# Arduino-Pro-Mini-xkid.net
KiCad netlist of a schematic drawn in EAGLE
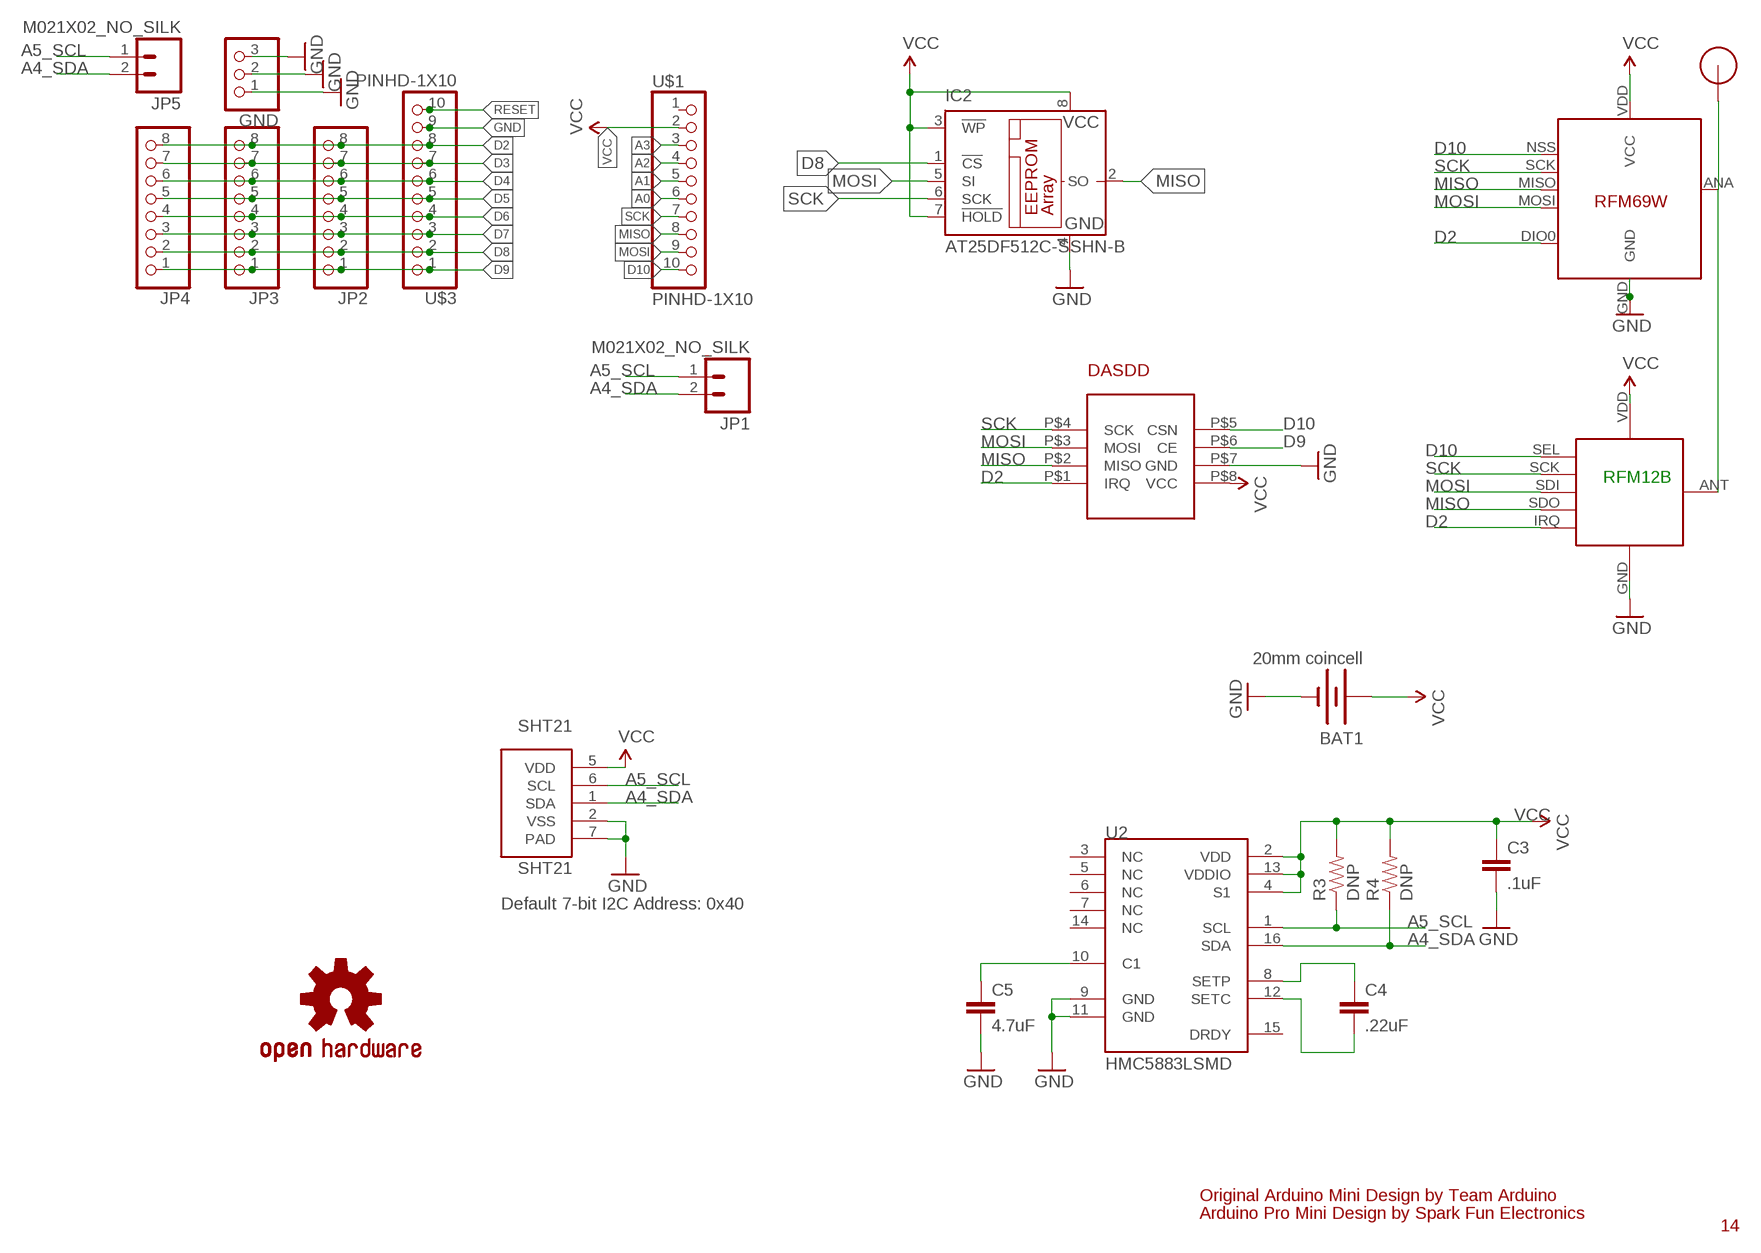
[diagram p0: schematic, sheet 1]

(export (version "E")
  (design (tool "Eeschema 10.0.6"))
  (components
    (comp (ref "BAT1")
      (value "20mm coincell")
      (footprint "eagle-import:BATTCON_20MM_4LEGS")
      (libsource (lib "eagle-import") (part "BATTERY20MM_4LEGS"))
    )
    (comp (ref "C3")
      (value ".1uF")
      (footprint "eagle-import:0603-CAP")
      (libsource (lib "eagle-import") (part "CAP0603-CAP"))
    )
    (comp (ref "C4")
      (value ".22uF")
      (footprint "eagle-import:0603-CAP")
      (libsource (lib "eagle-import") (part "CAP0603-CAP"))
    )
    (comp (ref "C5")
      (value "4.7uF")
      (footprint "eagle-import:0603-CAP")
      (libsource (lib "eagle-import") (part "CAP0603-CAP"))
    )
    (comp (ref "DASDD")
      (value "NRF24L01+_1.27")
      (footprint "eagle-import:NRF24L01_1.27")
      (libsource (lib "eagle-import") (part "NRF24L01+_1.27"))
    )
    (comp (ref "GND")
      (value "PINHD-1X3")
      (footprint "eagle-import:1X03")
      (libsource (lib "eagle-import") (part "PINHD-1X3"))
    )
    (comp (ref "IC2")
      (value "AT25DF512C-SSHN-B")
      (footprint "eagle-import:SO-08")
      (fields (field (name "MF") "MICROCHIP") (field (name "MPN") "25AA080/SN"))
      (libsource (lib "eagle-import") (part "25SNAA080"))
    )
    (comp (ref "JP1")
      (value "M021X02_NO_SILK")
      (footprint "eagle-import:1X02_NO_SILK")
      (libsource (lib "eagle-import") (part "M021X02_NO_SILK"))
    )
    (comp (ref "JP2")
      (value "PINHD-1X8CLEANBIG")
      (footprint "eagle-import:1X08-CLEANBIG")
      (libsource (lib "eagle-import") (part "PINHD-1X8CLEANBIG"))
    )
    (comp (ref "JP3")
      (value "PINHD-1X8CLEANBIG")
      (footprint "eagle-import:1X08-CLEANBIG")
      (libsource (lib "eagle-import") (part "PINHD-1X8CLEANBIG"))
    )
    (comp (ref "JP4")
      (value "PINHD-1X8CLEANBIG")
      (footprint "eagle-import:1X08-CLEANBIG")
      (libsource (lib "eagle-import") (part "PINHD-1X8CLEANBIG"))
    )
    (comp (ref "JP5")
      (value "M021X02_NO_SILK")
      (footprint "eagle-import:1X02_NO_SILK")
      (libsource (lib "eagle-import") (part "M021X02_NO_SILK"))
    )
    (comp (ref "LOGO1")
      (value "OSHW-LOGOM")
      (footprint "eagle-import:OSHW-LOGO-M")
      (libsource (lib "eagle-import") (part "OSHW-LOGOM"))
    )
    (comp (ref "R3")
      (value "DNP")
      (footprint "eagle-import:0603-RES")
      (libsource (lib "eagle-import") (part "RESISTOR0603-RES"))
    )
    (comp (ref "R4")
      (value "DNP")
      (footprint "eagle-import:0603-RES")
      (libsource (lib "eagle-import") (part "RESISTOR0603-RES"))
    )
    (comp (ref "RFM12B")
      (value "RFM12B_MINPADS")
      (footprint "eagle-import:RFM12B-MINPADS")
      (libsource (lib "eagle-import") (part "RFM12B_MINPADS"))
    )
    (comp (ref "RFM69W")
      (value "RFM69")
      (footprint "eagle-import:RFM69W-MINPADS")
      (libsource (lib "eagle-import") (part "RFM69"))
    )
    (comp (ref "SHT21")
      (value "SHT21")
      (footprint "eagle-import:SEN-SENSIRION-SHT2X")
      (libsource (lib "eagle-import") (part "SEN-SENSIRION-SHT2X"))
    )
    (comp (ref "U$1")
      (value "PINHD-1X10")
      (footprint "eagle-import:1X10-BIG")
      (libsource (lib "eagle-import") (part "PINHD-1X10"))
    )
    (comp (ref "U$3")
      (value "PINHD-1X10")
      (footprint "eagle-import:1X10-BIG")
      (libsource (lib "eagle-import") (part "PINHD-1X10"))
    )
    (comp (ref "U$4")
      (value "RFM12B_ANTENNA")
      (footprint "eagle-import:RFM12B-ANTENNA")
      (libsource (lib "eagle-import") (part "RFM12B_ANTENNA"))
    )
    (comp (ref "U2")
      (value "HMC5883LSMD")
      (footprint "eagle-import:16LPCC")
      (libsource (lib "eagle-import") (part "HMC5883LSMD"))
    )
  )
  (nets
    (net (code "1") (name "/A4_SDA") (class "Default")
      (node (ref "JP1") (pin "2") (pinfunction "2_2") (pintype "passive"))
      (node (ref "JP5") (pin "2") (pinfunction "2_2") (pintype "passive"))
      (node (ref "R4") (pin "1") (pinfunction "1_1") (pintype "passive"))
      (node (ref "SHT21") (pin "1") (pinfunction "SDA_1") (pintype "bidirectional"))
      (node (ref "U2") (pin "16") (pinfunction "SDA_16") (pintype "bidirectional"))
    )
    (net (code "2") (name "/A5_SCL") (class "Default")
      (node (ref "JP1") (pin "1") (pinfunction "1_1") (pintype "passive"))
      (node (ref "JP5") (pin "1") (pinfunction "1_1") (pintype "passive"))
      (node (ref "R3") (pin "1") (pinfunction "1_1") (pintype "passive"))
      (node (ref "SHT21") (pin "6") (pinfunction "SCL_6") (pintype "bidirectional"))
      (node (ref "U2") (pin "1") (pinfunction "SCL_1") (pintype "bidirectional"))
    )
    (net (code "3") (name "A0") (class "Default")
      (node (ref "U$1") (pin "6") (pinfunction "6_6") (pintype "passive"))
    )
    (net (code "4") (name "A1") (class "Default")
      (node (ref "U$1") (pin "5") (pinfunction "5_5") (pintype "passive"))
    )
    (net (code "5") (name "A2") (class "Default")
      (node (ref "U$1") (pin "4") (pinfunction "4_4") (pintype "passive"))
    )
    (net (code "6") (name "A3") (class "Default")
      (node (ref "U$1") (pin "3") (pinfunction "3_3") (pintype "passive"))
    )
    (net (code "7") (name "D2") (class "Default")
      (node (ref "DASDD") (pin "P$1") (pinfunction "IRQ_P$1") (pintype "bidirectional"))
      (node (ref "JP2") (pin "8") (pinfunction "8_8") (pintype "passive"))
      (node (ref "JP3") (pin "8") (pinfunction "8_8") (pintype "passive"))
      (node (ref "JP4") (pin "8") (pinfunction "8_8") (pintype "passive"))
      (node (ref "RFM12B") (pin "IRQ") (pinfunction "IRQ_IRQ") (pintype "bidirectional"))
      (node (ref "RFM69W") (pin "DIO0") (pinfunction "DIO0_DIO0") (pintype "open_collector"))
      (node (ref "U$3") (pin "8") (pinfunction "8_8") (pintype "passive"))
    )
    (net (code "8") (name "D3") (class "Default")
      (node (ref "JP2") (pin "7") (pinfunction "7_7") (pintype "passive"))
      (node (ref "JP3") (pin "7") (pinfunction "7_7") (pintype "passive"))
      (node (ref "JP4") (pin "7") (pinfunction "7_7") (pintype "passive"))
      (node (ref "U$3") (pin "7") (pinfunction "7_7") (pintype "passive"))
    )
    (net (code "9") (name "D4") (class "Default")
      (node (ref "JP2") (pin "6") (pinfunction "6_6") (pintype "passive"))
      (node (ref "JP3") (pin "6") (pinfunction "6_6") (pintype "passive"))
      (node (ref "JP4") (pin "6") (pinfunction "6_6") (pintype "passive"))
      (node (ref "U$3") (pin "6") (pinfunction "6_6") (pintype "passive"))
    )
    (net (code "10") (name "D5") (class "Default")
      (node (ref "JP2") (pin "5") (pinfunction "5_5") (pintype "passive"))
      (node (ref "JP3") (pin "5") (pinfunction "5_5") (pintype "passive"))
      (node (ref "JP4") (pin "5") (pinfunction "5_5") (pintype "passive"))
      (node (ref "U$3") (pin "5") (pinfunction "5_5") (pintype "passive"))
    )
    (net (code "11") (name "D6") (class "Default")
      (node (ref "JP2") (pin "4") (pinfunction "4_4") (pintype "passive"))
      (node (ref "JP3") (pin "4") (pinfunction "4_4") (pintype "passive"))
      (node (ref "JP4") (pin "4") (pinfunction "4_4") (pintype "passive"))
      (node (ref "U$3") (pin "4") (pinfunction "4_4") (pintype "passive"))
    )
    (net (code "12") (name "D7") (class "Default")
      (node (ref "JP2") (pin "3") (pinfunction "3_3") (pintype "passive"))
      (node (ref "JP3") (pin "3") (pinfunction "3_3") (pintype "passive"))
      (node (ref "JP4") (pin "3") (pinfunction "3_3") (pintype "passive"))
      (node (ref "U$3") (pin "3") (pinfunction "3_3") (pintype "passive"))
    )
    (net (code "13") (name "D8") (class "Default")
      (node (ref "IC2") (pin "1") (pinfunction "~{CS}_1") (pintype "input"))
      (node (ref "JP2") (pin "2") (pinfunction "2_2") (pintype "passive"))
      (node (ref "JP3") (pin "2") (pinfunction "2_2") (pintype "passive"))
      (node (ref "JP4") (pin "2") (pinfunction "2_2") (pintype "passive"))
      (node (ref "U$3") (pin "2") (pinfunction "2_2") (pintype "passive"))
    )
    (net (code "14") (name "D9") (class "Default")
      (node (ref "DASDD") (pin "P$6") (pinfunction "CE_P$6") (pintype "bidirectional"))
      (node (ref "JP2") (pin "1") (pinfunction "1_1") (pintype "passive"))
      (node (ref "JP3") (pin "1") (pinfunction "1_1") (pintype "passive"))
      (node (ref "JP4") (pin "1") (pinfunction "1_1") (pintype "passive"))
      (node (ref "U$3") (pin "1") (pinfunction "1_1") (pintype "passive"))
    )
    (net (code "15") (name "D10") (class "Default")
      (node (ref "DASDD") (pin "P$5") (pinfunction "CSN_P$5") (pintype "bidirectional"))
      (node (ref "RFM12B") (pin "SEL") (pinfunction "SEL_SEL") (pintype "bidirectional"))
      (node (ref "RFM69W") (pin "NSS") (pinfunction "SEL_NSS") (pintype "input"))
      (node (ref "U$1") (pin "10") (pinfunction "10_10") (pintype "passive"))
    )
    (net (code "16") (name "GND") (class "Default")
      (node (ref "BAT1") (pin "2") (pinfunction "-_2") (pintype "power_in"))
      (node (ref "C3") (pin "2") (pinfunction "2_2") (pintype "passive"))
      (node (ref "C5") (pin "2") (pinfunction "2_2") (pintype "passive"))
      (node (ref "DASDD") (pin "P$7") (pinfunction "GND_P$7") (pintype "bidirectional"))
      (node (ref "GND") (pin "1") (pinfunction "1_1") (pintype "passive"))
      (node (ref "GND") (pin "2") (pinfunction "2_2") (pintype "passive"))
      (node (ref "GND") (pin "3") (pinfunction "3_3") (pintype "passive"))
      (node (ref "IC2") (pin "4") (pinfunction "GND_4") (pintype "power_in"))
      (node (ref "RFM12B") (pin "GND") (pinfunction "GND_GND") (pintype "bidirectional"))
      (node (ref "RFM69W") (pin "GND") (pinfunction "GND_GND") (pintype "power_in"))
      (node (ref "SHT21") (pin "2") (pinfunction "VSS_2") (pintype "bidirectional"))
      (node (ref "SHT21") (pin "7") (pinfunction "PAD_7") (pintype "bidirectional"))
      (node (ref "U$3") (pin "9") (pinfunction "9_9") (pintype "passive"))
      (node (ref "U2") (pin "11") (pinfunction "GND_11") (pintype "bidirectional"))
      (node (ref "U2") (pin "9") (pinfunction "GND_9") (pintype "bidirectional"))
    )
    (net (code "17") (name "MISO") (class "Default")
      (node (ref "DASDD") (pin "P$2") (pinfunction "MISO_P$2") (pintype "bidirectional"))
      (node (ref "IC2") (pin "2") (pinfunction "SO_2") (pintype "bidirectional"))
      (node (ref "RFM12B") (pin "SDO") (pinfunction "SDO/MISO_SDO") (pintype "bidirectional"))
      (node (ref "RFM69W") (pin "MISO") (pinfunction "MISO_MISO") (pintype "input"))
      (node (ref "U$1") (pin "8") (pinfunction "8_8") (pintype "passive"))
    )
    (net (code "18") (name "MOSI") (class "Default")
      (node (ref "DASDD") (pin "P$3") (pinfunction "MOSI_P$3") (pintype "bidirectional"))
      (node (ref "IC2") (pin "5") (pinfunction "SI_5") (pintype "input"))
      (node (ref "RFM12B") (pin "SDI") (pinfunction "SDI/MOSI_SDI") (pintype "bidirectional"))
      (node (ref "RFM69W") (pin "MOSI") (pinfunction "MOSI_MOSI") (pintype "output"))
      (node (ref "U$1") (pin "9") (pinfunction "9_9") (pintype "passive"))
    )
    (net (code "19") (name "Net-(RFM69W-ANT)") (class "Default")
      (node (ref "RFM12B") (pin "ANT") (pinfunction "ANT_ANT") (pintype "bidirectional"))
      (node (ref "RFM69W") (pin "ANA") (pinfunction "ANT_ANA") (pintype "passive"))
      (node (ref "U$4") (pin "P$1") (pinfunction "1_P$1") (pintype "bidirectional"))
    )
    (net (code "20") (name "Net-(U2-C1)") (class "Default")
      (node (ref "C5") (pin "1") (pinfunction "1_1") (pintype "passive"))
      (node (ref "U2") (pin "10") (pinfunction "C1_10") (pintype "bidirectional"))
    )
    (net (code "21") (name "Net-(U2-SETC)") (class "Default")
      (node (ref "C4") (pin "2") (pinfunction "2_2") (pintype "passive"))
      (node (ref "U2") (pin "12") (pinfunction "SETC_12") (pintype "bidirectional"))
    )
    (net (code "22") (name "Net-(U2-SETP)") (class "Default")
      (node (ref "C4") (pin "1") (pinfunction "1_1") (pintype "passive"))
      (node (ref "U2") (pin "8") (pinfunction "SETP_8") (pintype "bidirectional"))
    )
    (net (code "23") (name "RESET") (class "Default")
      (node (ref "U$3") (pin "10") (pinfunction "10_10") (pintype "passive"))
    )
    (net (code "24") (name "SCK") (class "Default")
      (node (ref "DASDD") (pin "P$4") (pinfunction "SCK_P$4") (pintype "bidirectional"))
      (node (ref "IC2") (pin "6") (pinfunction "SCK_6") (pintype "input"))
      (node (ref "RFM12B") (pin "SCK") (pinfunction "SCK_SCK") (pintype "bidirectional"))
      (node (ref "RFM69W") (pin "SCK") (pinfunction "SCK_SCK") (pintype "input"))
      (node (ref "U$1") (pin "7") (pinfunction "7_7") (pintype "passive"))
    )
    (net (code "25") (name "VCC") (class "Default")
      (node (ref "BAT1") (pin "1") (pinfunction "+_1") (pintype "power_in"))
      (node (ref "C3") (pin "1") (pinfunction "1_1") (pintype "passive"))
      (node (ref "DASDD") (pin "P$8") (pinfunction "VCC_P$8") (pintype "bidirectional"))
      (node (ref "IC2") (pin "3") (pinfunction "~{WP}_3") (pintype "input"))
      (node (ref "IC2") (pin "7") (pinfunction "~{HOLD}_7") (pintype "input"))
      (node (ref "IC2") (pin "8") (pinfunction "VCC_8") (pintype "power_in"))
      (node (ref "R3") (pin "2") (pinfunction "2_2") (pintype "passive"))
      (node (ref "R4") (pin "2") (pinfunction "2_2") (pintype "passive"))
      (node (ref "RFM12B") (pin "VDD") (pinfunction "VDD_VDD") (pintype "bidirectional"))
      (node (ref "RFM69W") (pin "VDD") (pinfunction "VCC_VDD") (pintype "power_in"))
      (node (ref "SHT21") (pin "5") (pinfunction "VDD_5") (pintype "bidirectional"))
      (node (ref "U$1") (pin "2") (pinfunction "2_2") (pintype "passive"))
      (node (ref "U2") (pin "13") (pinfunction "VDDIO_13") (pintype "bidirectional"))
      (node (ref "U2") (pin "2") (pinfunction "VDD_2") (pintype "bidirectional"))
      (node (ref "U2") (pin "4") (pinfunction "S1_4") (pintype "bidirectional"))
    )
    (net (code "26") (name "unconnected-(U$1-Pad1)") (class "Default")
      (node (ref "U$1") (pin "1") (pinfunction "1_1") (pintype "passive"))
    )
    (net (code "27") (name "unconnected-(U2-DRDY-Pad15)") (class "Default")
      (node (ref "U2") (pin "15") (pinfunction "DRDY_15") (pintype "bidirectional"))
    )
    (net (code "28") (name "unconnected-(U2-NC-Pad3)") (class "Default")
      (node (ref "U2") (pin "3") (pinfunction "NC_3") (pintype "bidirectional"))
    )
    (net (code "29") (name "unconnected-(U2-NC-Pad5)") (class "Default")
      (node (ref "U2") (pin "5") (pinfunction "NC_5") (pintype "bidirectional"))
    )
    (net (code "30") (name "unconnected-(U2-NC-Pad6)") (class "Default")
      (node (ref "U2") (pin "6") (pinfunction "NC_6") (pintype "bidirectional"))
    )
    (net (code "31") (name "unconnected-(U2-NC-Pad7)") (class "Default")
      (node (ref "U2") (pin "7") (pinfunction "NC_7") (pintype "bidirectional"))
    )
    (net (code "32") (name "unconnected-(U2-NC-Pad14)") (class "Default")
      (node (ref "U2") (pin "14") (pinfunction "NC_14") (pintype "bidirectional"))
    )
  )
)
